# LCD_Camera_Connectors.net
KiCad netlist of a schematic drawn in Altium Designer
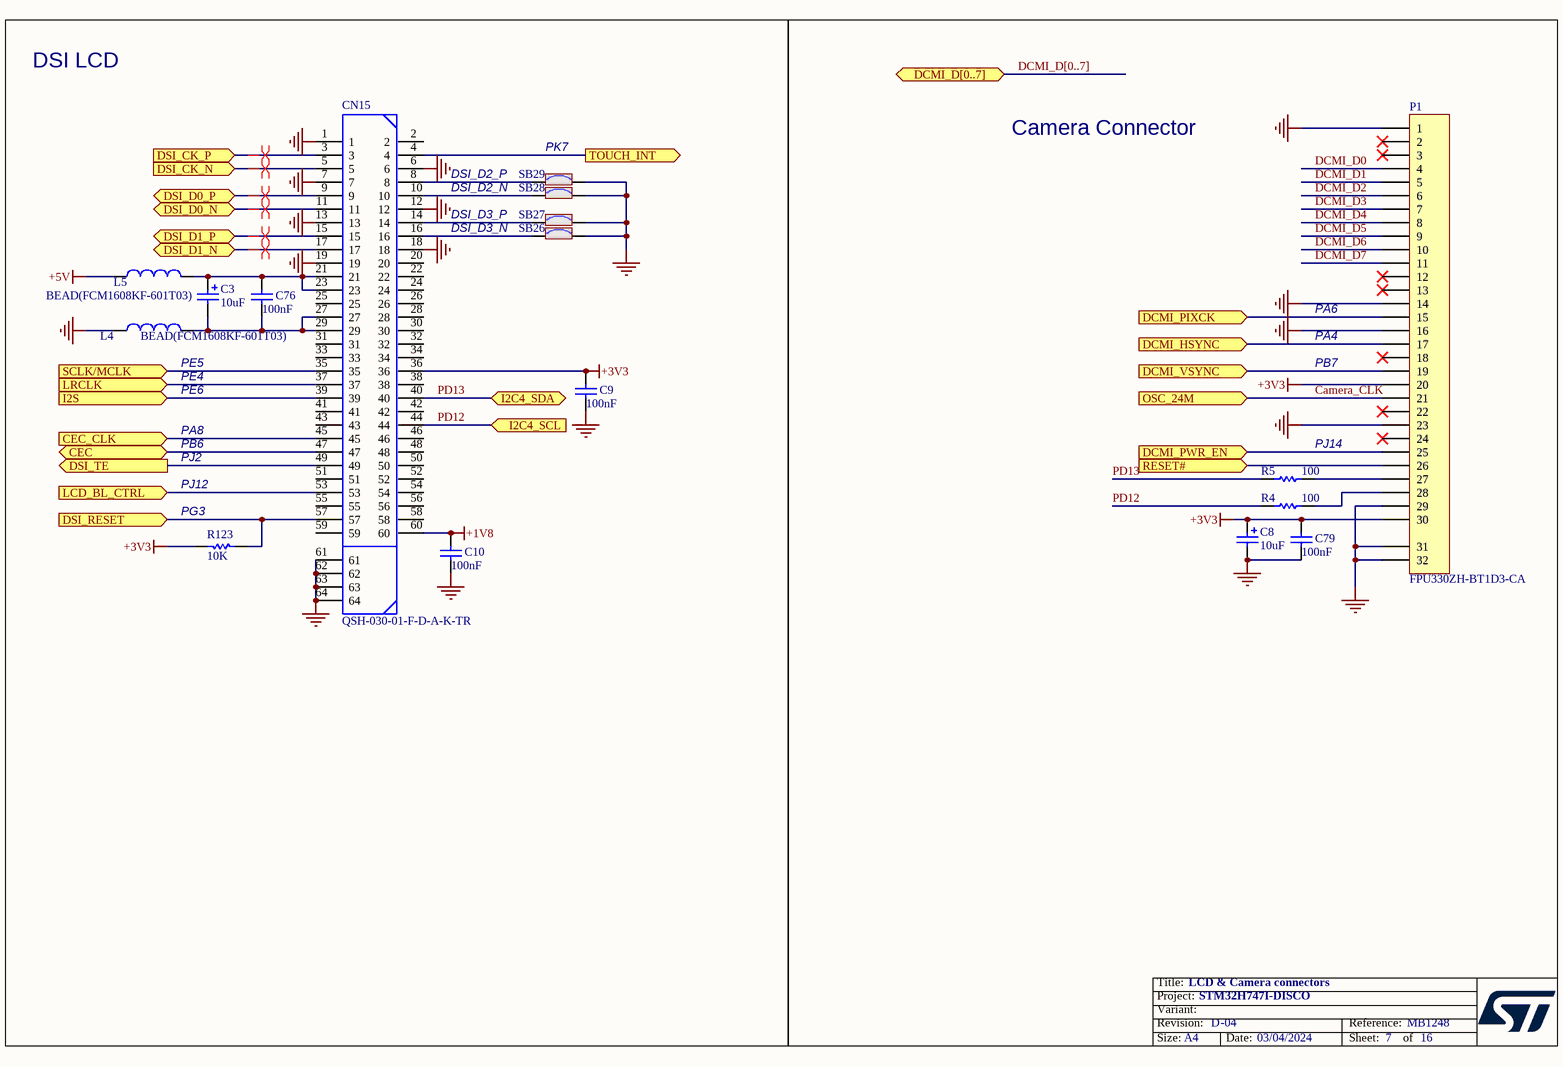
[diagram p0: LCD&Camera Connectors.SchDoc]

(export (version "E")
  (design (tool "Eeschema 10.0.6"))
  (components
    (comp (ref "C3")
      (value "10uF")
      (footprint "TAN-A")
      (description "Polarized Capacitor,10uF,10V,10%,typeA,VISHAY")
      (libsource (lib "MCD_TOOLS") (part "Cap_10uF_POL_10%_TANA"))
    )
    (comp (ref "C8")
      (value "10uF")
      (footprint "TAN-A")
      (description "Polarized Capacitor,10uF,10V,10%,typeA,VISHAY")
      (libsource (lib "MCD_TOOLS") (part "Cap_10uF_POL_10%_TANA"))
    )
    (comp (ref "C9")
      (value "100nF")
      (footprint "0603C")
      (description "Capacitor")
      (fields (field (name "PUBLISHER") "Altium Limited"))
      (libsource (lib "Miscellaneous Devices") (part "Cap"))
    )
    (comp (ref "C10")
      (value "100nF")
      (footprint "0603C")
      (description "Capacitor")
      (fields (field (name "PUBLISHER") "Altium Limited"))
      (libsource (lib "Miscellaneous Devices") (part "Cap"))
    )
    (comp (ref "C76")
      (value "100nF")
      (footprint "0603C")
      (description "Capacitor")
      (fields (field (name "PUBLISHER") "Altium Limited"))
      (libsource (lib "Miscellaneous Devices") (part "Cap"))
    )
    (comp (ref "C79")
      (value "100nF")
      (footprint "0603C")
      (description "Capacitor,100nF,16V,X7R,10%,0402,YAGEO")
      (libsource (lib "MCD_TOOLS") (part "Cap_100nF_X7R_10%_0402"))
    )
    (comp (ref "CN15")
      (value "QSH-030-01-F-D-A-K-TR")
      (footprint "QSH-030-01-F-D-A")
      (description "HIGH SPEED SOCKET STRIP, .5mm PITCH, 60 PINS")
      (fields (field (name "MANUFACTURER") "SAMTEC") (field (name "CREATED") "28 JAN 2014 - WENDY XIN"))
      (libsource (lib "MB1166") (part "QSH-030-01-F-D-A"))
    )
    (comp (ref "L4")
      (value "BEAD(FCM1608KF-601T03)")
      (footprint "0603L")
      (description "Inductor")
      (fields (field (name "PUBLISHER") "Altium Limited"))
      (libsource (lib "Miscellaneous Devices") (part "Inductor"))
    )
    (comp (ref "L5")
      (value "BEAD(FCM1608KF-601T03)")
      (footprint "0603L")
      (description "Inductor")
      (fields (field (name "PUBLISHER") "Altium Limited"))
      (libsource (lib "Miscellaneous Devices") (part "Inductor"))
    )
    (comp (ref "P1")
      (value "FPU330ZH-BT1D3-CA")
      (footprint "FPU330ZH-BT1D3-CA")
      (description "TOWNES -  Connector FFC/FPC ZIF 0.5mm 30 pins, Lower Contacts")
      (libsource (lib "MB1248_1") (part "FPU330ZH-BT1D3-CA"))
    )
    (comp (ref "R4")
      (value "100")
      (footprint "0603R")
      (description "Resistor,100,0402,1%,YAGEO")
      (libsource (lib "MCD_TOOLS") (part "Res_100_1%_0402"))
    )
    (comp (ref "R5")
      (value "100")
      (footprint "0603R")
      (description "Resistor,100,0402,1%,YAGEO")
      (libsource (lib "MCD_TOOLS") (part "Res_100_1%_0402"))
    )
    (comp (ref "R123")
      (value "10K")
      (footprint "0603R")
      (description "Resistor")
      (fields (field (name "PUBLISHER") "Altium Limited"))
      (libsource (lib "Miscellaneous Devices") (part "Res1"))
    )
    (comp (ref "SB26")
      (value "Solder Bridge ON")
      (footprint "SB_0603")
      (libsource (lib "MCD_TOOLS") (part "SB_ON"))
    )
    (comp (ref "SB27")
      (value "Solder Bridge ON")
      (footprint "SB_0603")
      (libsource (lib "MCD_TOOLS") (part "SB_ON"))
    )
    (comp (ref "SB28")
      (value "Solder Bridge ON")
      (footprint "SB_0603")
      (libsource (lib "MCD_TOOLS") (part "SB_ON"))
    )
    (comp (ref "SB29")
      (value "Solder Bridge ON")
      (footprint "SB_0603")
      (libsource (lib "MCD_TOOLS") (part "SB_ON"))
    )
  )
  (nets
    (net (code "1") (name "+1V8") (class "Default")
      (node (ref "C10") (pin "1") (pinfunction "1_1") (pintype "passive"))
      (node (ref "CN15") (pin "60") (pinfunction "60_60") (pintype "passive"))
    )
    (net (code "2") (name "+3V3") (class "Default")
      (node (ref "C79") (pin "2") (pinfunction "2_2") (pintype "passive"))
      (node (ref "C8") (pin "1") (pinfunction "1_1") (pintype "passive"))
      (node (ref "C9") (pin "1") (pinfunction "1_1") (pintype "passive"))
      (node (ref "CN15") (pin "36") (pinfunction "36_36") (pintype "passive"))
      (node (ref "P1") (pin "20") (pinfunction "20_20") (pintype "passive"))
      (node (ref "P1") (pin "30") (pinfunction "30_30") (pintype "passive"))
      (node (ref "R123") (pin "2") (pinfunction "2_2") (pintype "passive"))
    )
    (net (code "3") (name "+5V") (class "Default")
      (node (ref "L5") (pin "1") (pinfunction "1_1") (pintype "passive"))
    )
    (net (code "4") (name "/CEC") (class "Default")
      (node (ref "CN15") (pin "47") (pinfunction "47_47") (pintype "passive"))
    )
    (net (code "5") (name "/CEC_CLK") (class "Default")
      (node (ref "CN15") (pin "45") (pinfunction "45_45") (pintype "passive"))
    )
    (net (code "6") (name "/Camera_CLK") (class "Default")
      (node (ref "P1") (pin "21") (pinfunction "21_21") (pintype "passive"))
    )
    (net (code "7") (name "/DCMI_D0") (class "Default")
      (node (ref "P1") (pin "4") (pinfunction "4_4") (pintype "passive"))
    )
    (net (code "8") (name "/DCMI_D1") (class "Default")
      (node (ref "P1") (pin "5") (pinfunction "5_5") (pintype "passive"))
    )
    (net (code "9") (name "/DCMI_D2") (class "Default")
      (node (ref "P1") (pin "6") (pinfunction "6_6") (pintype "passive"))
    )
    (net (code "10") (name "/DCMI_D3") (class "Default")
      (node (ref "P1") (pin "7") (pinfunction "7_7") (pintype "passive"))
    )
    (net (code "11") (name "/DCMI_D4") (class "Default")
      (node (ref "P1") (pin "8") (pinfunction "8_8") (pintype "passive"))
    )
    (net (code "12") (name "/DCMI_D5") (class "Default")
      (node (ref "P1") (pin "9") (pinfunction "9_9") (pintype "passive"))
    )
    (net (code "13") (name "/DCMI_D6") (class "Default")
      (node (ref "P1") (pin "10") (pinfunction "10_10") (pintype "passive"))
    )
    (net (code "14") (name "/DCMI_D7") (class "Default")
      (node (ref "P1") (pin "11") (pinfunction "11_11") (pintype "passive"))
    )
    (net (code "16") (name "/DCMI_HSYNC") (class "Default")
      (node (ref "P1") (pin "17") (pinfunction "17_17") (pintype "passive"))
    )
    (net (code "17") (name "/DCMI_PIXCK") (class "Default")
      (node (ref "P1") (pin "15") (pinfunction "15_15") (pintype "passive"))
    )
    (net (code "18") (name "/DCMI_PWR_EN") (class "Default")
      (node (ref "P1") (pin "25") (pinfunction "25_25") (pintype "passive"))
    )
    (net (code "19") (name "/DCMI_VSYNC") (class "Default")
      (node (ref "P1") (pin "19") (pinfunction "19_19") (pintype "passive"))
    )
    (net (code "20") (name "/DSI_CK_N") (class "Default")
      (node (ref "CN15") (pin "5") (pinfunction "5_5") (pintype "passive"))
    )
    (net (code "21") (name "/DSI_CK_P") (class "Default")
      (node (ref "CN15") (pin "3") (pinfunction "3_3") (pintype "passive"))
    )
    (net (code "22") (name "/DSI_D0_N") (class "Default")
      (node (ref "CN15") (pin "11") (pinfunction "11_11") (pintype "passive"))
    )
    (net (code "23") (name "/DSI_D0_P") (class "Default")
      (node (ref "CN15") (pin "9") (pinfunction "9_9") (pintype "passive"))
    )
    (net (code "24") (name "/DSI_D1_N") (class "Default")
      (node (ref "CN15") (pin "17") (pinfunction "17_17") (pintype "passive"))
    )
    (net (code "25") (name "/DSI_D1_P") (class "Default")
      (node (ref "CN15") (pin "15") (pinfunction "15_15") (pintype "passive"))
    )
    (net (code "26") (name "/DSI_RESET") (class "Default")
      (node (ref "CN15") (pin "57") (pinfunction "57_57") (pintype "passive"))
      (node (ref "R123") (pin "1") (pinfunction "1_1") (pintype "passive"))
    )
    (net (code "27") (name "/DSI_TE") (class "Default")
      (node (ref "CN15") (pin "49") (pinfunction "49_49") (pintype "passive"))
    )
    (net (code "28") (name "/I2S") (class "Default")
      (node (ref "CN15") (pin "39") (pinfunction "39_39") (pintype "passive"))
    )
    (net (code "29") (name "/LCD_BL_CTRL") (class "Default")
      (node (ref "CN15") (pin "53") (pinfunction "53_53") (pintype "passive"))
    )
    (net (code "30") (name "/LRCLK") (class "Default")
      (node (ref "CN15") (pin "37") (pinfunction "37_37") (pintype "passive"))
    )
    (net (code "31") (name "/PD12") (class "Default")
      (node (ref "CN15") (pin "44") (pinfunction "44_44") (pintype "passive"))
      (node (ref "R4") (pin "1") (pinfunction "1_1") (pintype "passive"))
    )
    (net (code "32") (name "/PD13") (class "Default")
      (node (ref "CN15") (pin "40") (pinfunction "40_40") (pintype "passive"))
      (node (ref "R5") (pin "1") (pinfunction "1_1") (pintype "passive"))
    )
    (net (code "33") (name "/RESET#") (class "Default")
      (node (ref "P1") (pin "26") (pinfunction "26_26") (pintype "passive"))
    )
    (net (code "34") (name "/SCLK{slash}MCLK") (class "Default")
      (node (ref "CN15") (pin "35") (pinfunction "35_35") (pintype "passive"))
    )
    (net (code "35") (name "/TOUCH_INT") (class "Default")
      (node (ref "CN15") (pin "4") (pinfunction "4_4") (pintype "passive"))
    )
    (net (code "36") (name "GND") (class "Default")
      (node (ref "C10") (pin "2") (pinfunction "2_2") (pintype "passive"))
      (node (ref "C79") (pin "1") (pinfunction "1_1") (pintype "passive"))
      (node (ref "C8") (pin "2") (pinfunction "2_2") (pintype "passive"))
      (node (ref "C9") (pin "2") (pinfunction "2_2") (pintype "passive"))
      (node (ref "CN15") (pin "1") (pinfunction "1_1") (pintype "passive"))
      (node (ref "CN15") (pin "12") (pinfunction "12_12") (pintype "passive"))
      (node (ref "CN15") (pin "13") (pinfunction "13_13") (pintype "passive"))
      (node (ref "CN15") (pin "18") (pinfunction "18_18") (pintype "passive"))
      (node (ref "CN15") (pin "19") (pinfunction "19_19") (pintype "passive"))
      (node (ref "CN15") (pin "6") (pinfunction "6_6") (pintype "passive"))
      (node (ref "CN15") (pin "61") (pinfunction "61_61") (pintype "passive"))
      (node (ref "CN15") (pin "62") (pinfunction "62_62") (pintype "passive"))
      (node (ref "CN15") (pin "63") (pinfunction "63_63") (pintype "passive"))
      (node (ref "CN15") (pin "64") (pinfunction "64_64") (pintype "passive"))
      (node (ref "CN15") (pin "7") (pinfunction "7_7") (pintype "passive"))
      (node (ref "L4") (pin "1") (pinfunction "1_1") (pintype "passive"))
      (node (ref "P1") (pin "1") (pinfunction "1_1") (pintype "passive"))
      (node (ref "P1") (pin "14") (pinfunction "14_14") (pintype "passive"))
      (node (ref "P1") (pin "16") (pinfunction "16_16") (pintype "passive"))
      (node (ref "P1") (pin "23") (pinfunction "23_23") (pintype "passive"))
      (node (ref "P1") (pin "29") (pinfunction "29_29") (pintype "passive"))
      (node (ref "P1") (pin "31") (pinfunction "31_31") (pintype "passive"))
      (node (ref "P1") (pin "32") (pinfunction "32_32") (pintype "passive"))
      (node (ref "SB26") (pin "2") (pinfunction "2_2") (pintype "passive"))
      (node (ref "SB27") (pin "2") (pinfunction "2_2") (pintype "passive"))
      (node (ref "SB28") (pin "2") (pinfunction "2_2") (pintype "passive"))
      (node (ref "SB29") (pin "2") (pinfunction "2_2") (pintype "passive"))
    )
    (net (code "37") (name "Net-(C3-Pad1)") (class "Default")
      (node (ref "C3") (pin "1") (pinfunction "1_1") (pintype "passive"))
      (node (ref "C76") (pin "1") (pinfunction "1_1") (pintype "passive"))
      (node (ref "CN15") (pin "21") (pinfunction "21_21") (pintype "passive"))
      (node (ref "CN15") (pin "23") (pinfunction "23_23") (pintype "passive"))
      (node (ref "L5") (pin "2") (pinfunction "2_2") (pintype "passive"))
    )
    (net (code "38") (name "Net-(C3-Pad2)") (class "Default")
      (node (ref "C3") (pin "2") (pinfunction "2_2") (pintype "passive"))
      (node (ref "C76") (pin "2") (pinfunction "2_2") (pintype "passive"))
      (node (ref "CN15") (pin "27") (pinfunction "27_27") (pintype "passive"))
      (node (ref "CN15") (pin "29") (pinfunction "29_29") (pintype "passive"))
      (node (ref "L4") (pin "2") (pinfunction "2_2") (pintype "passive"))
    )
    (net (code "39") (name "Net-(CN15-Pad8)") (class "Default")
      (node (ref "CN15") (pin "8") (pinfunction "8_8") (pintype "passive"))
      (node (ref "SB29") (pin "1") (pinfunction "1_1") (pintype "passive"))
    )
    (net (code "40") (name "Net-(CN15-Pad10)") (class "Default")
      (node (ref "CN15") (pin "10") (pinfunction "10_10") (pintype "passive"))
      (node (ref "SB28") (pin "1") (pinfunction "1_1") (pintype "passive"))
    )
    (net (code "41") (name "Net-(CN15-Pad14)") (class "Default")
      (node (ref "CN15") (pin "14") (pinfunction "14_14") (pintype "passive"))
      (node (ref "SB27") (pin "1") (pinfunction "1_1") (pintype "passive"))
    )
    (net (code "42") (name "Net-(CN15-Pad16)") (class "Default")
      (node (ref "CN15") (pin "16") (pinfunction "16_16") (pintype "passive"))
      (node (ref "SB26") (pin "1") (pinfunction "1_1") (pintype "passive"))
    )
    (net (code "43") (name "Net-(P1-Pad27)") (class "Default")
      (node (ref "P1") (pin "27") (pinfunction "27_27") (pintype "passive"))
      (node (ref "R5") (pin "2") (pinfunction "2_2") (pintype "passive"))
    )
    (net (code "44") (name "Net-(P1-Pad28)") (class "Default")
      (node (ref "P1") (pin "28") (pinfunction "28_28") (pintype "passive"))
      (node (ref "R4") (pin "2") (pinfunction "2_2") (pintype "passive"))
    )
    (net (code "45") (name "unconnected-(CN15-Pad2)") (class "Default")
      (node (ref "CN15") (pin "2") (pinfunction "2_2") (pintype "passive"))
    )
    (net (code "46") (name "unconnected-(CN15-Pad20)") (class "Default")
      (node (ref "CN15") (pin "20") (pinfunction "20_20") (pintype "passive"))
    )
    (net (code "47") (name "unconnected-(CN15-Pad22)") (class "Default")
      (node (ref "CN15") (pin "22") (pinfunction "22_22") (pintype "passive"))
    )
    (net (code "48") (name "unconnected-(CN15-Pad24)") (class "Default")
      (node (ref "CN15") (pin "24") (pinfunction "24_24") (pintype "passive"))
    )
    (net (code "49") (name "unconnected-(CN15-Pad25)") (class "Default")
      (node (ref "CN15") (pin "25") (pinfunction "25_25") (pintype "passive"))
    )
    (net (code "50") (name "unconnected-(CN15-Pad26)") (class "Default")
      (node (ref "CN15") (pin "26") (pinfunction "26_26") (pintype "passive"))
    )
    (net (code "51") (name "unconnected-(CN15-Pad28)") (class "Default")
      (node (ref "CN15") (pin "28") (pinfunction "28_28") (pintype "passive"))
    )
    (net (code "52") (name "unconnected-(CN15-Pad30)") (class "Default")
      (node (ref "CN15") (pin "30") (pinfunction "30_30") (pintype "passive"))
    )
    (net (code "53") (name "unconnected-(CN15-Pad31)") (class "Default")
      (node (ref "CN15") (pin "31") (pinfunction "31_31") (pintype "passive"))
    )
    (net (code "54") (name "unconnected-(CN15-Pad32)") (class "Default")
      (node (ref "CN15") (pin "32") (pinfunction "32_32") (pintype "passive"))
    )
    (net (code "55") (name "unconnected-(CN15-Pad33)") (class "Default")
      (node (ref "CN15") (pin "33") (pinfunction "33_33") (pintype "passive"))
    )
    (net (code "56") (name "unconnected-(CN15-Pad34)") (class "Default")
      (node (ref "CN15") (pin "34") (pinfunction "34_34") (pintype "passive"))
    )
    (net (code "57") (name "unconnected-(CN15-Pad38)") (class "Default")
      (node (ref "CN15") (pin "38") (pinfunction "38_38") (pintype "passive"))
    )
    (net (code "58") (name "unconnected-(CN15-Pad41)") (class "Default")
      (node (ref "CN15") (pin "41") (pinfunction "41_41") (pintype "passive"))
    )
    (net (code "59") (name "unconnected-(CN15-Pad42)") (class "Default")
      (node (ref "CN15") (pin "42") (pinfunction "42_42") (pintype "passive"))
    )
    (net (code "60") (name "unconnected-(CN15-Pad43)") (class "Default")
      (node (ref "CN15") (pin "43") (pinfunction "43_43") (pintype "passive"))
    )
    (net (code "61") (name "unconnected-(CN15-Pad46)") (class "Default")
      (node (ref "CN15") (pin "46") (pinfunction "46_46") (pintype "passive"))
    )
    (net (code "62") (name "unconnected-(CN15-Pad48)") (class "Default")
      (node (ref "CN15") (pin "48") (pinfunction "48_48") (pintype "passive"))
    )
    (net (code "63") (name "unconnected-(CN15-Pad50)") (class "Default")
      (node (ref "CN15") (pin "50") (pinfunction "50_50") (pintype "passive"))
    )
    (net (code "64") (name "unconnected-(CN15-Pad51)") (class "Default")
      (node (ref "CN15") (pin "51") (pinfunction "51_51") (pintype "passive"))
    )
    (net (code "65") (name "unconnected-(CN15-Pad52)") (class "Default")
      (node (ref "CN15") (pin "52") (pinfunction "52_52") (pintype "passive"))
    )
    (net (code "66") (name "unconnected-(CN15-Pad54)") (class "Default")
      (node (ref "CN15") (pin "54") (pinfunction "54_54") (pintype "passive"))
    )
    (net (code "67") (name "unconnected-(CN15-Pad55)") (class "Default")
      (node (ref "CN15") (pin "55") (pinfunction "55_55") (pintype "passive"))
    )
    (net (code "68") (name "unconnected-(CN15-Pad56)") (class "Default")
      (node (ref "CN15") (pin "56") (pinfunction "56_56") (pintype "passive"))
    )
    (net (code "69") (name "unconnected-(CN15-Pad58)") (class "Default")
      (node (ref "CN15") (pin "58") (pinfunction "58_58") (pintype "passive"))
    )
    (net (code "70") (name "unconnected-(CN15-Pad59)") (class "Default")
      (node (ref "CN15") (pin "59") (pinfunction "59_59") (pintype "passive"))
    )
    (net (code "71") (name "unconnected-(P1-Pad2)") (class "Default")
      (node (ref "P1") (pin "2") (pinfunction "2_2") (pintype "passive+no_connect"))
    )
    (net (code "72") (name "unconnected-(P1-Pad3)") (class "Default")
      (node (ref "P1") (pin "3") (pinfunction "3_3") (pintype "passive+no_connect"))
    )
    (net (code "73") (name "unconnected-(P1-Pad12)") (class "Default")
      (node (ref "P1") (pin "12") (pinfunction "12_12") (pintype "passive+no_connect"))
    )
    (net (code "74") (name "unconnected-(P1-Pad13)") (class "Default")
      (node (ref "P1") (pin "13") (pinfunction "13_13") (pintype "passive+no_connect"))
    )
    (net (code "75") (name "unconnected-(P1-Pad18)") (class "Default")
      (node (ref "P1") (pin "18") (pinfunction "18_18") (pintype "passive+no_connect"))
    )
    (net (code "76") (name "unconnected-(P1-Pad22)") (class "Default")
      (node (ref "P1") (pin "22") (pinfunction "22_22") (pintype "passive+no_connect"))
    )
    (net (code "77") (name "unconnected-(P1-Pad24)") (class "Default")
      (node (ref "P1") (pin "24") (pinfunction "24_24") (pintype "passive+no_connect"))
    )
  )
)
